# Chov2_led.net
KiCad netlist of a schematic drawn in Altium Designer
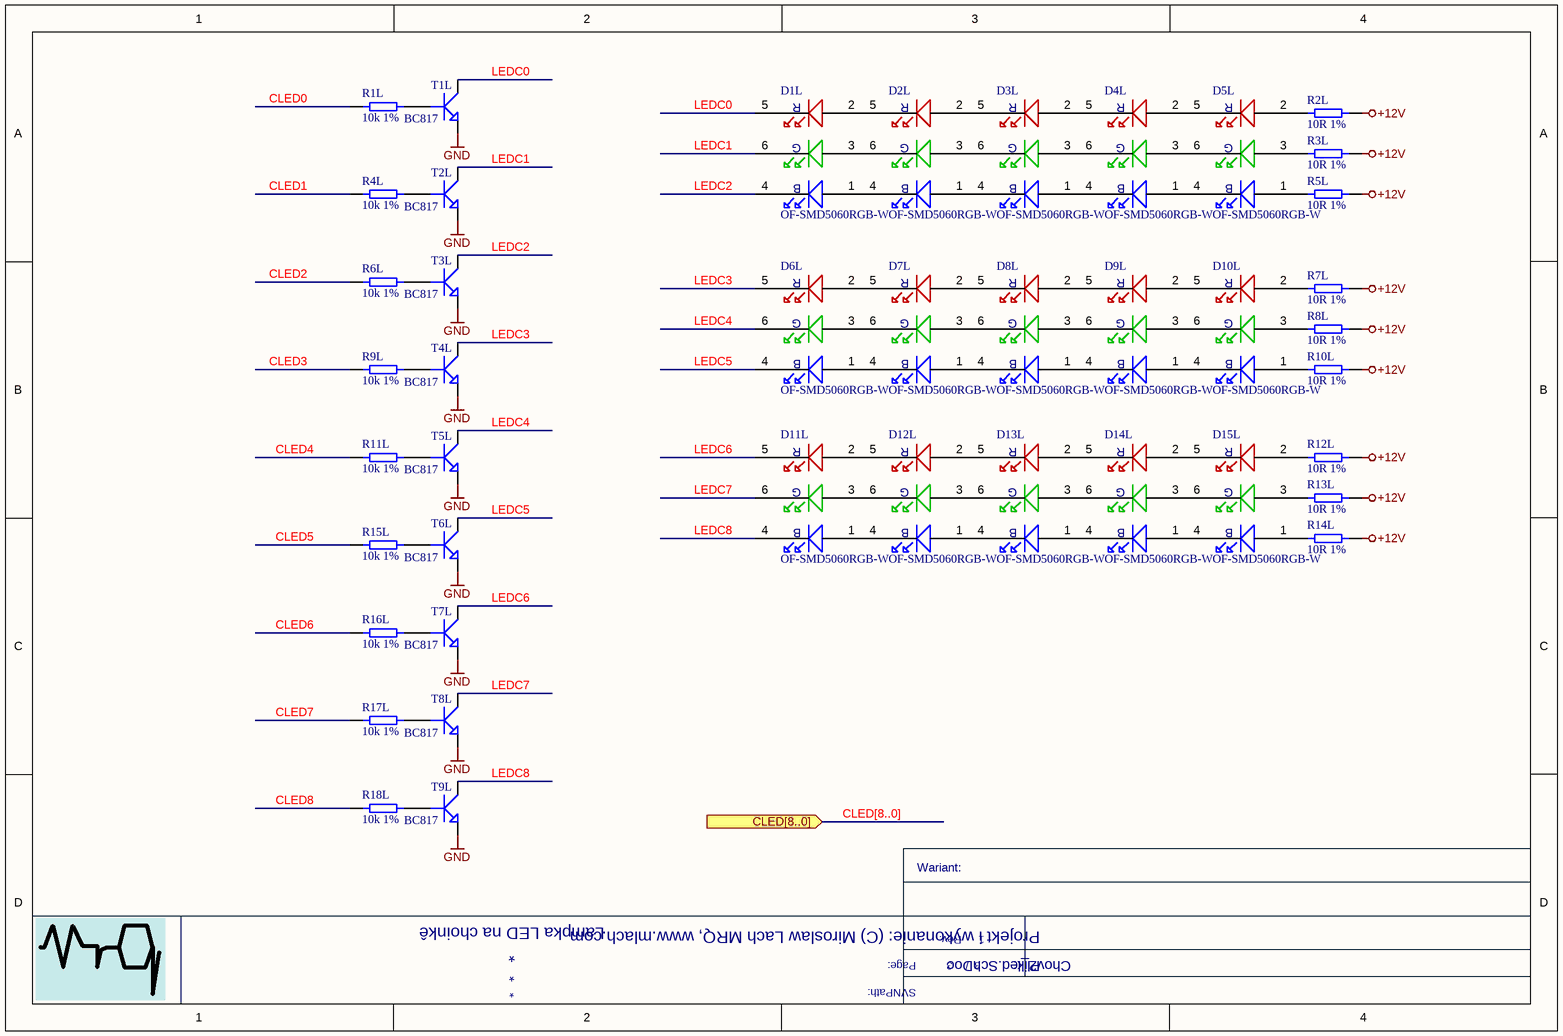
[diagram p0: Chov2_led.SchDoc]

(export (version "E")
  (design (tool "Eeschema 10.0.6"))
  (components
    (comp (ref "D1L")
      (value "OF-SMD5060RGB-W")
      (footprint "OF-SMD5060RGB-W")
      (libsource (lib "Parts") (part "OF-SMD5060RGB-W"))
    )
    (comp (ref "D2L")
      (value "OF-SMD5060RGB-W")
      (footprint "OF-SMD5060RGB-W")
      (libsource (lib "Parts") (part "OF-SMD5060RGB-W"))
    )
    (comp (ref "D3L")
      (value "OF-SMD5060RGB-W")
      (footprint "OF-SMD5060RGB-W")
      (libsource (lib "Parts") (part "OF-SMD5060RGB-W"))
    )
    (comp (ref "D4L")
      (value "OF-SMD5060RGB-W")
      (footprint "OF-SMD5060RGB-W")
      (libsource (lib "Parts") (part "OF-SMD5060RGB-W"))
    )
    (comp (ref "D5L")
      (value "OF-SMD5060RGB-W")
      (footprint "OF-SMD5060RGB-W")
      (libsource (lib "Parts") (part "OF-SMD5060RGB-W"))
    )
    (comp (ref "D6L")
      (value "OF-SMD5060RGB-W")
      (footprint "OF-SMD5060RGB-W")
      (libsource (lib "Parts") (part "OF-SMD5060RGB-W"))
    )
    (comp (ref "D7L")
      (value "OF-SMD5060RGB-W")
      (footprint "OF-SMD5060RGB-W")
      (libsource (lib "Parts") (part "OF-SMD5060RGB-W"))
    )
    (comp (ref "D8L")
      (value "OF-SMD5060RGB-W")
      (footprint "OF-SMD5060RGB-W")
      (libsource (lib "Parts") (part "OF-SMD5060RGB-W"))
    )
    (comp (ref "D9L")
      (value "OF-SMD5060RGB-W")
      (footprint "OF-SMD5060RGB-W")
      (libsource (lib "Parts") (part "OF-SMD5060RGB-W"))
    )
    (comp (ref "D10L")
      (value "OF-SMD5060RGB-W")
      (footprint "OF-SMD5060RGB-W")
      (libsource (lib "Parts") (part "OF-SMD5060RGB-W"))
    )
    (comp (ref "D11L")
      (value "OF-SMD5060RGB-W")
      (footprint "OF-SMD5060RGB-W")
      (libsource (lib "Parts") (part "OF-SMD5060RGB-W"))
    )
    (comp (ref "D12L")
      (value "OF-SMD5060RGB-W")
      (footprint "OF-SMD5060RGB-W")
      (libsource (lib "Parts") (part "OF-SMD5060RGB-W"))
    )
    (comp (ref "D13L")
      (value "OF-SMD5060RGB-W")
      (footprint "OF-SMD5060RGB-W")
      (libsource (lib "Parts") (part "OF-SMD5060RGB-W"))
    )
    (comp (ref "D14L")
      (value "OF-SMD5060RGB-W")
      (footprint "OF-SMD5060RGB-W")
      (libsource (lib "Parts") (part "OF-SMD5060RGB-W"))
    )
    (comp (ref "D15L")
      (value "OF-SMD5060RGB-W")
      (footprint "OF-SMD5060RGB-W")
      (libsource (lib "Parts") (part "OF-SMD5060RGB-W"))
    )
    (comp (ref "R1L")
      (value "0603WGF10KT5E")
      (footprint "0603-IPC")
      (fields (field (name "OTHERPARAMS") "10k 1%") (field (name "TOLERANCE") "1%"))
      (libsource (lib "Parts") (part "R"))
    )
    (comp (ref "R2L")
      (value "0805S8F100JT5E")
      (footprint "0805")
      (fields (field (name "OTHERPARAMS") "10R 1%") (field (name "TOLERANCE") "1%"))
      (libsource (lib "Parts") (part "R"))
    )
    (comp (ref "R3L")
      (value "0805S8F100JT5E")
      (footprint "0805")
      (fields (field (name "OTHERPARAMS") "10R 1%") (field (name "TOLERANCE") "1%"))
      (libsource (lib "Parts") (part "R"))
    )
    (comp (ref "R4L")
      (value "0603WGF10KT5E")
      (footprint "0603-IPC")
      (fields (field (name "OTHERPARAMS") "10k 1%") (field (name "TOLERANCE") "1%"))
      (libsource (lib "Parts") (part "R"))
    )
    (comp (ref "R5L")
      (value "0805S8F100JT5E")
      (footprint "0805")
      (fields (field (name "OTHERPARAMS") "10R 1%") (field (name "TOLERANCE") "1%"))
      (libsource (lib "Parts") (part "R"))
    )
    (comp (ref "R6L")
      (value "0603WGF10KT5E")
      (footprint "0603-IPC")
      (fields (field (name "OTHERPARAMS") "10k 1%") (field (name "TOLERANCE") "1%"))
      (libsource (lib "Parts") (part "R"))
    )
    (comp (ref "R7L")
      (value "0805S8F100JT5E")
      (footprint "0805")
      (fields (field (name "OTHERPARAMS") "10R 1%") (field (name "TOLERANCE") "1%"))
      (libsource (lib "Parts") (part "R"))
    )
    (comp (ref "R8L")
      (value "0805S8F100JT5E")
      (footprint "0805")
      (fields (field (name "OTHERPARAMS") "10R 1%") (field (name "TOLERANCE") "1%"))
      (libsource (lib "Parts") (part "R"))
    )
    (comp (ref "R9L")
      (value "0603WGF10KT5E")
      (footprint "0603-IPC")
      (fields (field (name "OTHERPARAMS") "10k 1%") (field (name "TOLERANCE") "1%"))
      (libsource (lib "Parts") (part "R"))
    )
    (comp (ref "R10L")
      (value "0805S8F100JT5E")
      (footprint "0805")
      (fields (field (name "OTHERPARAMS") "10R 1%") (field (name "TOLERANCE") "1%"))
      (libsource (lib "Parts") (part "R"))
    )
    (comp (ref "R11L")
      (value "0603WGF10KT5E")
      (footprint "0603-IPC")
      (fields (field (name "OTHERPARAMS") "10k 1%") (field (name "TOLERANCE") "1%"))
      (libsource (lib "Parts") (part "R"))
    )
    (comp (ref "R12L")
      (value "0805S8F100JT5E")
      (footprint "0805")
      (fields (field (name "OTHERPARAMS") "10R 1%") (field (name "TOLERANCE") "1%"))
      (libsource (lib "Parts") (part "R"))
    )
    (comp (ref "R13L")
      (value "0805S8F100JT5E")
      (footprint "0805")
      (fields (field (name "OTHERPARAMS") "10R 1%") (field (name "TOLERANCE") "1%"))
      (libsource (lib "Parts") (part "R"))
    )
    (comp (ref "R14L")
      (value "0805S8F100JT5E")
      (footprint "0805")
      (fields (field (name "OTHERPARAMS") "10R 1%") (field (name "TOLERANCE") "1%"))
      (libsource (lib "Parts") (part "R"))
    )
    (comp (ref "R15L")
      (value "0603WGF10KT5E")
      (footprint "0603-IPC")
      (fields (field (name "OTHERPARAMS") "10k 1%") (field (name "TOLERANCE") "1%"))
      (libsource (lib "Parts") (part "R"))
    )
    (comp (ref "R16L")
      (value "0603WGF10KT5E")
      (footprint "0603-IPC")
      (fields (field (name "OTHERPARAMS") "10k 1%") (field (name "TOLERANCE") "1%"))
      (libsource (lib "Parts") (part "R"))
    )
    (comp (ref "R17L")
      (value "0603WGF10KT5E")
      (footprint "0603-IPC")
      (fields (field (name "OTHERPARAMS") "10k 1%") (field (name "TOLERANCE") "1%"))
      (libsource (lib "Parts") (part "R"))
    )
    (comp (ref "R18L")
      (value "0603WGF10KT5E")
      (footprint "0603-IPC")
      (fields (field (name "OTHERPARAMS") "10k 1%") (field (name "TOLERANCE") "1%"))
      (libsource (lib "Parts") (part "R"))
    )
    (comp (ref "T1L") (value "BC817") (footprint "SOT23-3") (libsource (lib "Parts") (part "NPN_SOT23-3")))
    (comp (ref "T2L") (value "BC817") (footprint "SOT23-3") (libsource (lib "Parts") (part "NPN_SOT23-3")))
    (comp (ref "T3L") (value "BC817") (footprint "SOT23-3") (libsource (lib "Parts") (part "NPN_SOT23-3")))
    (comp (ref "T4L") (value "BC817") (footprint "SOT23-3") (libsource (lib "Parts") (part "NPN_SOT23-3")))
    (comp (ref "T5L") (value "BC817") (footprint "SOT23-3") (libsource (lib "Parts") (part "NPN_SOT23-3")))
    (comp (ref "T6L") (value "BC817") (footprint "SOT23-3") (libsource (lib "Parts") (part "NPN_SOT23-3")))
    (comp (ref "T7L") (value "BC817") (footprint "SOT23-3") (libsource (lib "Parts") (part "NPN_SOT23-3")))
    (comp (ref "T8L") (value "BC817") (footprint "SOT23-3") (libsource (lib "Parts") (part "NPN_SOT23-3")))
    (comp (ref "T9L") (value "BC817") (footprint "SOT23-3") (libsource (lib "Parts") (part "NPN_SOT23-3")))
  )
  (nets
    (net (code "1") (name "+12V") (class "Default")
      (node (ref "R10L") (pin "2") (pinfunction "2_2") (pintype "passive"))
      (node (ref "R12L") (pin "2") (pinfunction "2_2") (pintype "passive"))
      (node (ref "R13L") (pin "2") (pinfunction "2_2") (pintype "passive"))
      (node (ref "R14L") (pin "2") (pinfunction "2_2") (pintype "passive"))
      (node (ref "R2L") (pin "2") (pinfunction "2_2") (pintype "passive"))
      (node (ref "R3L") (pin "2") (pinfunction "2_2") (pintype "passive"))
      (node (ref "R5L") (pin "2") (pinfunction "2_2") (pintype "passive"))
      (node (ref "R7L") (pin "2") (pinfunction "2_2") (pintype "passive"))
      (node (ref "R8L") (pin "2") (pinfunction "2_2") (pintype "passive"))
    )
    (net (code "2") (name "/CLED0") (class "Default")
      (node (ref "R1L") (pin "1") (pinfunction "1_1") (pintype "passive"))
    )
    (net (code "3") (name "/CLED1") (class "Default")
      (node (ref "R4L") (pin "1") (pinfunction "1_1") (pintype "passive"))
    )
    (net (code "4") (name "/CLED2") (class "Default")
      (node (ref "R6L") (pin "1") (pinfunction "1_1") (pintype "passive"))
    )
    (net (code "5") (name "/CLED3") (class "Default")
      (node (ref "R9L") (pin "1") (pinfunction "1_1") (pintype "passive"))
    )
    (net (code "6") (name "/CLED4") (class "Default")
      (node (ref "R11L") (pin "1") (pinfunction "1_1") (pintype "passive"))
    )
    (net (code "7") (name "/CLED5") (class "Default")
      (node (ref "R15L") (pin "1") (pinfunction "1_1") (pintype "passive"))
    )
    (net (code "8") (name "/CLED6") (class "Default")
      (node (ref "R16L") (pin "1") (pinfunction "1_1") (pintype "passive"))
    )
    (net (code "9") (name "/CLED7") (class "Default")
      (node (ref "R17L") (pin "1") (pinfunction "1_1") (pintype "passive"))
    )
    (net (code "10") (name "/CLED8") (class "Default")
      (node (ref "R18L") (pin "1") (pinfunction "1_1") (pintype "passive"))
    )
    (net (code "12") (name "/LEDC0") (class "Default")
      (node (ref "D1L") (pin "5") (pinfunction "CATH_5") (pintype "passive"))
      (node (ref "T1L") (pin "3") (pinfunction "3_3") (pintype "passive"))
    )
    (net (code "13") (name "/LEDC1") (class "Default")
      (node (ref "D1L") (pin "6") (pinfunction "CATH_6") (pintype "passive"))
      (node (ref "T2L") (pin "3") (pinfunction "3_3") (pintype "passive"))
    )
    (net (code "14") (name "/LEDC2") (class "Default")
      (node (ref "D1L") (pin "4") (pinfunction "CATH_4") (pintype "passive"))
      (node (ref "T3L") (pin "3") (pinfunction "3_3") (pintype "passive"))
    )
    (net (code "15") (name "/LEDC3") (class "Default")
      (node (ref "D6L") (pin "5") (pinfunction "CATH_5") (pintype "passive"))
      (node (ref "T4L") (pin "3") (pinfunction "3_3") (pintype "passive"))
    )
    (net (code "16") (name "/LEDC4") (class "Default")
      (node (ref "D6L") (pin "6") (pinfunction "CATH_6") (pintype "passive"))
      (node (ref "T5L") (pin "3") (pinfunction "3_3") (pintype "passive"))
    )
    (net (code "17") (name "/LEDC5") (class "Default")
      (node (ref "D6L") (pin "4") (pinfunction "CATH_4") (pintype "passive"))
      (node (ref "T6L") (pin "3") (pinfunction "3_3") (pintype "passive"))
    )
    (net (code "18") (name "/LEDC6") (class "Default")
      (node (ref "D11L") (pin "5") (pinfunction "CATH_5") (pintype "passive"))
      (node (ref "T7L") (pin "3") (pinfunction "3_3") (pintype "passive"))
    )
    (net (code "19") (name "/LEDC7") (class "Default")
      (node (ref "D11L") (pin "6") (pinfunction "CATH_6") (pintype "passive"))
      (node (ref "T8L") (pin "3") (pinfunction "3_3") (pintype "passive"))
    )
    (net (code "20") (name "/LEDC8") (class "Default")
      (node (ref "D11L") (pin "4") (pinfunction "CATH_4") (pintype "passive"))
      (node (ref "T9L") (pin "3") (pinfunction "3_3") (pintype "passive"))
    )
    (net (code "21") (name "GND") (class "Default")
      (node (ref "T1L") (pin "2") (pinfunction "2_2") (pintype "passive"))
      (node (ref "T2L") (pin "2") (pinfunction "2_2") (pintype "passive"))
      (node (ref "T3L") (pin "2") (pinfunction "2_2") (pintype "passive"))
      (node (ref "T4L") (pin "2") (pinfunction "2_2") (pintype "passive"))
      (node (ref "T5L") (pin "2") (pinfunction "2_2") (pintype "passive"))
      (node (ref "T6L") (pin "2") (pinfunction "2_2") (pintype "passive"))
      (node (ref "T7L") (pin "2") (pinfunction "2_2") (pintype "passive"))
      (node (ref "T8L") (pin "2") (pinfunction "2_2") (pintype "passive"))
      (node (ref "T9L") (pin "2") (pinfunction "2_2") (pintype "passive"))
    )
    (net (code "22") (name "Net-(D1L-ANOD-Pad1)") (class "Default")
      (node (ref "D1L") (pin "1") (pinfunction "ANOD_1") (pintype "passive"))
      (node (ref "D2L") (pin "4") (pinfunction "CATH_4") (pintype "passive"))
    )
    (net (code "23") (name "Net-(D1L-ANOD-Pad2)") (class "Default")
      (node (ref "D1L") (pin "2") (pinfunction "ANOD_2") (pintype "passive"))
      (node (ref "D2L") (pin "5") (pinfunction "CATH_5") (pintype "passive"))
    )
    (net (code "24") (name "Net-(D1L-ANOD-Pad3)") (class "Default")
      (node (ref "D1L") (pin "3") (pinfunction "ANOD_3") (pintype "passive"))
      (node (ref "D2L") (pin "6") (pinfunction "CATH_6") (pintype "passive"))
    )
    (net (code "25") (name "Net-(D2L-ANOD-Pad1)") (class "Default")
      (node (ref "D2L") (pin "1") (pinfunction "ANOD_1") (pintype "passive"))
      (node (ref "D3L") (pin "4") (pinfunction "CATH_4") (pintype "passive"))
    )
    (net (code "26") (name "Net-(D2L-ANOD-Pad2)") (class "Default")
      (node (ref "D2L") (pin "2") (pinfunction "ANOD_2") (pintype "passive"))
      (node (ref "D3L") (pin "5") (pinfunction "CATH_5") (pintype "passive"))
    )
    (net (code "27") (name "Net-(D2L-ANOD-Pad3)") (class "Default")
      (node (ref "D2L") (pin "3") (pinfunction "ANOD_3") (pintype "passive"))
      (node (ref "D3L") (pin "6") (pinfunction "CATH_6") (pintype "passive"))
    )
    (net (code "28") (name "Net-(D3L-ANOD-Pad1)") (class "Default")
      (node (ref "D3L") (pin "1") (pinfunction "ANOD_1") (pintype "passive"))
      (node (ref "D4L") (pin "4") (pinfunction "CATH_4") (pintype "passive"))
    )
    (net (code "29") (name "Net-(D3L-ANOD-Pad2)") (class "Default")
      (node (ref "D3L") (pin "2") (pinfunction "ANOD_2") (pintype "passive"))
      (node (ref "D4L") (pin "5") (pinfunction "CATH_5") (pintype "passive"))
    )
    (net (code "30") (name "Net-(D3L-ANOD-Pad3)") (class "Default")
      (node (ref "D3L") (pin "3") (pinfunction "ANOD_3") (pintype "passive"))
      (node (ref "D4L") (pin "6") (pinfunction "CATH_6") (pintype "passive"))
    )
    (net (code "31") (name "Net-(D4L-ANOD-Pad1)") (class "Default")
      (node (ref "D4L") (pin "1") (pinfunction "ANOD_1") (pintype "passive"))
      (node (ref "D5L") (pin "4") (pinfunction "CATH_4") (pintype "passive"))
    )
    (net (code "32") (name "Net-(D4L-ANOD-Pad2)") (class "Default")
      (node (ref "D4L") (pin "2") (pinfunction "ANOD_2") (pintype "passive"))
      (node (ref "D5L") (pin "5") (pinfunction "CATH_5") (pintype "passive"))
    )
    (net (code "33") (name "Net-(D4L-ANOD-Pad3)") (class "Default")
      (node (ref "D4L") (pin "3") (pinfunction "ANOD_3") (pintype "passive"))
      (node (ref "D5L") (pin "6") (pinfunction "CATH_6") (pintype "passive"))
    )
    (net (code "34") (name "Net-(D5L-ANOD-Pad1)") (class "Default")
      (node (ref "D5L") (pin "1") (pinfunction "ANOD_1") (pintype "passive"))
      (node (ref "R5L") (pin "1") (pinfunction "1_1") (pintype "passive"))
    )
    (net (code "35") (name "Net-(D5L-ANOD-Pad2)") (class "Default")
      (node (ref "D5L") (pin "2") (pinfunction "ANOD_2") (pintype "passive"))
      (node (ref "R2L") (pin "1") (pinfunction "1_1") (pintype "passive"))
    )
    (net (code "36") (name "Net-(D5L-ANOD-Pad3)") (class "Default")
      (node (ref "D5L") (pin "3") (pinfunction "ANOD_3") (pintype "passive"))
      (node (ref "R3L") (pin "1") (pinfunction "1_1") (pintype "passive"))
    )
    (net (code "37") (name "Net-(D6L-ANOD-Pad1)") (class "Default")
      (node (ref "D6L") (pin "1") (pinfunction "ANOD_1") (pintype "passive"))
      (node (ref "D7L") (pin "4") (pinfunction "CATH_4") (pintype "passive"))
    )
    (net (code "38") (name "Net-(D6L-ANOD-Pad2)") (class "Default")
      (node (ref "D6L") (pin "2") (pinfunction "ANOD_2") (pintype "passive"))
      (node (ref "D7L") (pin "5") (pinfunction "CATH_5") (pintype "passive"))
    )
    (net (code "39") (name "Net-(D6L-ANOD-Pad3)") (class "Default")
      (node (ref "D6L") (pin "3") (pinfunction "ANOD_3") (pintype "passive"))
      (node (ref "D7L") (pin "6") (pinfunction "CATH_6") (pintype "passive"))
    )
    (net (code "40") (name "Net-(D7L-ANOD-Pad1)") (class "Default")
      (node (ref "D7L") (pin "1") (pinfunction "ANOD_1") (pintype "passive"))
      (node (ref "D8L") (pin "4") (pinfunction "CATH_4") (pintype "passive"))
    )
    (net (code "41") (name "Net-(D7L-ANOD-Pad2)") (class "Default")
      (node (ref "D7L") (pin "2") (pinfunction "ANOD_2") (pintype "passive"))
      (node (ref "D8L") (pin "5") (pinfunction "CATH_5") (pintype "passive"))
    )
    (net (code "42") (name "Net-(D7L-ANOD-Pad3)") (class "Default")
      (node (ref "D7L") (pin "3") (pinfunction "ANOD_3") (pintype "passive"))
      (node (ref "D8L") (pin "6") (pinfunction "CATH_6") (pintype "passive"))
    )
    (net (code "43") (name "Net-(D8L-ANOD-Pad1)") (class "Default")
      (node (ref "D8L") (pin "1") (pinfunction "ANOD_1") (pintype "passive"))
      (node (ref "D9L") (pin "4") (pinfunction "CATH_4") (pintype "passive"))
    )
    (net (code "44") (name "Net-(D8L-ANOD-Pad2)") (class "Default")
      (node (ref "D8L") (pin "2") (pinfunction "ANOD_2") (pintype "passive"))
      (node (ref "D9L") (pin "5") (pinfunction "CATH_5") (pintype "passive"))
    )
    (net (code "45") (name "Net-(D8L-ANOD-Pad3)") (class "Default")
      (node (ref "D8L") (pin "3") (pinfunction "ANOD_3") (pintype "passive"))
      (node (ref "D9L") (pin "6") (pinfunction "CATH_6") (pintype "passive"))
    )
    (net (code "46") (name "Net-(D10L-ANOD-Pad1)") (class "Default")
      (node (ref "D10L") (pin "1") (pinfunction "ANOD_1") (pintype "passive"))
      (node (ref "R10L") (pin "1") (pinfunction "1_1") (pintype "passive"))
    )
    (net (code "47") (name "Net-(D10L-ANOD-Pad2)") (class "Default")
      (node (ref "D10L") (pin "2") (pinfunction "ANOD_2") (pintype "passive"))
      (node (ref "R7L") (pin "1") (pinfunction "1_1") (pintype "passive"))
    )
    (net (code "48") (name "Net-(D10L-ANOD-Pad3)") (class "Default")
      (node (ref "D10L") (pin "3") (pinfunction "ANOD_3") (pintype "passive"))
      (node (ref "R8L") (pin "1") (pinfunction "1_1") (pintype "passive"))
    )
    (net (code "49") (name "Net-(D10L-CATH-Pad4)") (class "Default")
      (node (ref "D10L") (pin "4") (pinfunction "CATH_4") (pintype "passive"))
      (node (ref "D9L") (pin "1") (pinfunction "ANOD_1") (pintype "passive"))
    )
    (net (code "50") (name "Net-(D10L-CATH-Pad5)") (class "Default")
      (node (ref "D10L") (pin "5") (pinfunction "CATH_5") (pintype "passive"))
      (node (ref "D9L") (pin "2") (pinfunction "ANOD_2") (pintype "passive"))
    )
    (net (code "51") (name "Net-(D10L-CATH-Pad6)") (class "Default")
      (node (ref "D10L") (pin "6") (pinfunction "CATH_6") (pintype "passive"))
      (node (ref "D9L") (pin "3") (pinfunction "ANOD_3") (pintype "passive"))
    )
    (net (code "52") (name "Net-(D11L-ANOD-Pad1)") (class "Default")
      (node (ref "D11L") (pin "1") (pinfunction "ANOD_1") (pintype "passive"))
      (node (ref "D12L") (pin "4") (pinfunction "CATH_4") (pintype "passive"))
    )
    (net (code "53") (name "Net-(D11L-ANOD-Pad2)") (class "Default")
      (node (ref "D11L") (pin "2") (pinfunction "ANOD_2") (pintype "passive"))
      (node (ref "D12L") (pin "5") (pinfunction "CATH_5") (pintype "passive"))
    )
    (net (code "54") (name "Net-(D11L-ANOD-Pad3)") (class "Default")
      (node (ref "D11L") (pin "3") (pinfunction "ANOD_3") (pintype "passive"))
      (node (ref "D12L") (pin "6") (pinfunction "CATH_6") (pintype "passive"))
    )
    (net (code "55") (name "Net-(D12L-ANOD-Pad1)") (class "Default")
      (node (ref "D12L") (pin "1") (pinfunction "ANOD_1") (pintype "passive"))
      (node (ref "D13L") (pin "4") (pinfunction "CATH_4") (pintype "passive"))
    )
    (net (code "56") (name "Net-(D12L-ANOD-Pad2)") (class "Default")
      (node (ref "D12L") (pin "2") (pinfunction "ANOD_2") (pintype "passive"))
      (node (ref "D13L") (pin "5") (pinfunction "CATH_5") (pintype "passive"))
    )
    (net (code "57") (name "Net-(D12L-ANOD-Pad3)") (class "Default")
      (node (ref "D12L") (pin "3") (pinfunction "ANOD_3") (pintype "passive"))
      (node (ref "D13L") (pin "6") (pinfunction "CATH_6") (pintype "passive"))
    )
    (net (code "58") (name "Net-(D13L-ANOD-Pad1)") (class "Default")
      (node (ref "D13L") (pin "1") (pinfunction "ANOD_1") (pintype "passive"))
      (node (ref "D14L") (pin "4") (pinfunction "CATH_4") (pintype "passive"))
    )
    (net (code "59") (name "Net-(D13L-ANOD-Pad2)") (class "Default")
      (node (ref "D13L") (pin "2") (pinfunction "ANOD_2") (pintype "passive"))
      (node (ref "D14L") (pin "5") (pinfunction "CATH_5") (pintype "passive"))
    )
    (net (code "60") (name "Net-(D13L-ANOD-Pad3)") (class "Default")
      (node (ref "D13L") (pin "3") (pinfunction "ANOD_3") (pintype "passive"))
      (node (ref "D14L") (pin "6") (pinfunction "CATH_6") (pintype "passive"))
    )
    (net (code "61") (name "Net-(D14L-ANOD-Pad1)") (class "Default")
      (node (ref "D14L") (pin "1") (pinfunction "ANOD_1") (pintype "passive"))
      (node (ref "D15L") (pin "4") (pinfunction "CATH_4") (pintype "passive"))
    )
    (net (code "62") (name "Net-(D14L-ANOD-Pad2)") (class "Default")
      (node (ref "D14L") (pin "2") (pinfunction "ANOD_2") (pintype "passive"))
      (node (ref "D15L") (pin "5") (pinfunction "CATH_5") (pintype "passive"))
    )
    (net (code "63") (name "Net-(D14L-ANOD-Pad3)") (class "Default")
      (node (ref "D14L") (pin "3") (pinfunction "ANOD_3") (pintype "passive"))
      (node (ref "D15L") (pin "6") (pinfunction "CATH_6") (pintype "passive"))
    )
    (net (code "64") (name "Net-(D15L-ANOD-Pad1)") (class "Default")
      (node (ref "D15L") (pin "1") (pinfunction "ANOD_1") (pintype "passive"))
      (node (ref "R14L") (pin "1") (pinfunction "1_1") (pintype "passive"))
    )
    (net (code "65") (name "Net-(D15L-ANOD-Pad2)") (class "Default")
      (node (ref "D15L") (pin "2") (pinfunction "ANOD_2") (pintype "passive"))
      (node (ref "R12L") (pin "1") (pinfunction "1_1") (pintype "passive"))
    )
    (net (code "66") (name "Net-(D15L-ANOD-Pad3)") (class "Default")
      (node (ref "D15L") (pin "3") (pinfunction "ANOD_3") (pintype "passive"))
      (node (ref "R13L") (pin "1") (pinfunction "1_1") (pintype "passive"))
    )
    (net (code "67") (name "Net-(R1L-Pad2)") (class "Default")
      (node (ref "R1L") (pin "2") (pinfunction "2_2") (pintype "passive"))
      (node (ref "T1L") (pin "1") (pinfunction "1_1") (pintype "passive"))
    )
    (net (code "68") (name "Net-(R4L-Pad2)") (class "Default")
      (node (ref "R4L") (pin "2") (pinfunction "2_2") (pintype "passive"))
      (node (ref "T2L") (pin "1") (pinfunction "1_1") (pintype "passive"))
    )
    (net (code "69") (name "Net-(R6L-Pad2)") (class "Default")
      (node (ref "R6L") (pin "2") (pinfunction "2_2") (pintype "passive"))
      (node (ref "T3L") (pin "1") (pinfunction "1_1") (pintype "passive"))
    )
    (net (code "70") (name "Net-(R9L-Pad2)") (class "Default")
      (node (ref "R9L") (pin "2") (pinfunction "2_2") (pintype "passive"))
      (node (ref "T4L") (pin "1") (pinfunction "1_1") (pintype "passive"))
    )
    (net (code "71") (name "Net-(R11L-Pad2)") (class "Default")
      (node (ref "R11L") (pin "2") (pinfunction "2_2") (pintype "passive"))
      (node (ref "T5L") (pin "1") (pinfunction "1_1") (pintype "passive"))
    )
    (net (code "72") (name "Net-(R15L-Pad2)") (class "Default")
      (node (ref "R15L") (pin "2") (pinfunction "2_2") (pintype "passive"))
      (node (ref "T6L") (pin "1") (pinfunction "1_1") (pintype "passive"))
    )
    (net (code "73") (name "Net-(R16L-Pad2)") (class "Default")
      (node (ref "R16L") (pin "2") (pinfunction "2_2") (pintype "passive"))
      (node (ref "T7L") (pin "1") (pinfunction "1_1") (pintype "passive"))
    )
    (net (code "74") (name "Net-(R17L-Pad2)") (class "Default")
      (node (ref "R17L") (pin "2") (pinfunction "2_2") (pintype "passive"))
      (node (ref "T8L") (pin "1") (pinfunction "1_1") (pintype "passive"))
    )
    (net (code "75") (name "Net-(R18L-Pad2)") (class "Default")
      (node (ref "R18L") (pin "2") (pinfunction "2_2") (pintype "passive"))
      (node (ref "T9L") (pin "1") (pinfunction "1_1") (pintype "passive"))
    )
  )
)
